# 555_led_blink.net
KiCad netlist of a schematic drawn in EAGLE
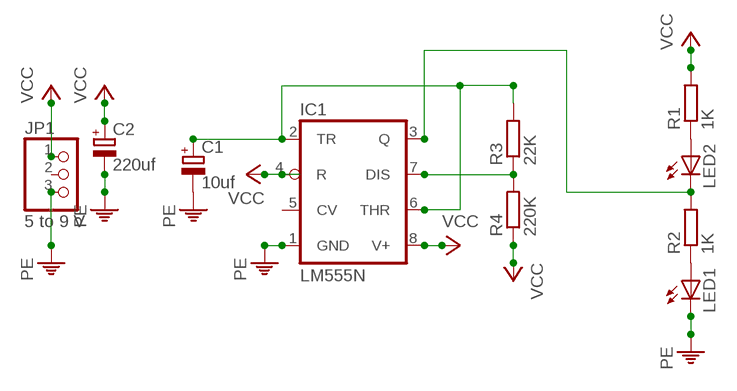
[diagram p0: schematic, sheet 1]

(export (version "E")
  (design (tool "Eeschema 10.0.6"))
  (components
    (comp (ref "C1")
      (value "10uf")
      (footprint "eagle-import:B45181B")
      (libsource (lib "eagle-import") (part "CPOL-EUB45181B"))
    )
    (comp (ref "C2")
      (value "220uf")
      (footprint "eagle-import:B45181B")
      (libsource (lib "eagle-import") (part "CPOL-EUB45181B"))
    )
    (comp (ref "IC1")
      (value "LM555N")
      (footprint "eagle-import:DIL08")
      (libsource (lib "eagle-import") (part "555NLM"))
    )
    (comp (ref "JP1")
      (value "5 to 9 V")
      (footprint "eagle-import:1X03")
      (libsource (lib "eagle-import") (part "PINHD-1X3"))
    )
    (comp (ref "LED1")
      (value "LED5MM")
      (footprint "eagle-import:LED5MM")
      (libsource (lib "eagle-import") (part "LED5MM"))
    )
    (comp (ref "LED2")
      (value "LED5MM")
      (footprint "eagle-import:LED5MM")
      (libsource (lib "eagle-import") (part "LED5MM"))
    )
    (comp (ref "R1")
      (value "1K")
      (footprint "eagle-import:0207_10")
      (libsource (lib "eagle-import") (part "R-EU_0207/10"))
    )
    (comp (ref "R2")
      (value "1K")
      (footprint "eagle-import:0207_10")
      (libsource (lib "eagle-import") (part "R-EU_0207/10"))
    )
    (comp (ref "R3")
      (value "22K")
      (footprint "eagle-import:0207_10")
      (libsource (lib "eagle-import") (part "R-EU_0207/10"))
    )
    (comp (ref "R4")
      (value "220K")
      (footprint "eagle-import:0207_10")
      (libsource (lib "eagle-import") (part "R-EU_0207/10"))
    )
  )
  (nets
    (net (code "1") (name "Net-(IC1-DIS)") (class "Default")
      (node (ref "IC1") (pin "7") (pinfunction "DIS_7") (pintype "input"))
      (node (ref "R3") (pin "1") (pinfunction "1_1") (pintype "passive"))
      (node (ref "R4") (pin "2") (pinfunction "2_2") (pintype "passive"))
    )
    (net (code "2") (name "Net-(IC1-Q)") (class "Default")
      (node (ref "IC1") (pin "3") (pinfunction "Q_3") (pintype "output"))
      (node (ref "LED2") (pin "K") (pinfunction "C_K") (pintype "passive"))
      (node (ref "R2") (pin "2") (pinfunction "2_2") (pintype "passive"))
    )
    (net (code "3") (name "Net-(IC1-THR)") (class "Default")
      (node (ref "C1") (pin "+") (pinfunction "+_+") (pintype "passive"))
      (node (ref "IC1") (pin "2") (pinfunction "TR_2") (pintype "input"))
      (node (ref "IC1") (pin "6") (pinfunction "THR_6") (pintype "input"))
      (node (ref "R3") (pin "2") (pinfunction "2_2") (pintype "passive"))
    )
    (net (code "4") (name "Net-(LED1-PadA)") (class "Default")
      (node (ref "LED1") (pin "A") (pinfunction "A_A") (pintype "passive"))
      (node (ref "R2") (pin "1") (pinfunction "1_1") (pintype "passive"))
    )
    (net (code "5") (name "Net-(LED2-PadA)") (class "Default")
      (node (ref "LED2") (pin "A") (pinfunction "A_A") (pintype "passive"))
      (node (ref "R1") (pin "1") (pinfunction "1_1") (pintype "passive"))
    )
    (net (code "6") (name "PE") (class "Default")
      (node (ref "C1") (pin "-") (pinfunction "-_-") (pintype "passive"))
      (node (ref "C2") (pin "-") (pinfunction "-_-") (pintype "passive"))
      (node (ref "IC1") (pin "1") (pinfunction "GND_1") (pintype "power_in"))
      (node (ref "JP1") (pin "3") (pinfunction "3_3") (pintype "passive"))
      (node (ref "LED1") (pin "K") (pinfunction "C_K") (pintype "passive"))
    )
    (net (code "7") (name "VCC") (class "Default")
      (node (ref "C2") (pin "+") (pinfunction "+_+") (pintype "passive"))
      (node (ref "IC1") (pin "4") (pinfunction "R_4") (pintype "input"))
      (node (ref "IC1") (pin "8") (pinfunction "V+_8") (pintype "power_in"))
      (node (ref "JP1") (pin "1") (pinfunction "1_1") (pintype "passive"))
      (node (ref "R1") (pin "2") (pinfunction "2_2") (pintype "passive"))
      (node (ref "R4") (pin "1") (pinfunction "1_1") (pintype "passive"))
    )
    (net (code "8") (name "unconnected-(IC1-CV-Pad5)") (class "Default")
      (node (ref "IC1") (pin "5") (pinfunction "CV_5") (pintype "input"))
    )
    (net (code "9") (name "unconnected-(JP1-Pad2)") (class "Default")
      (node (ref "JP1") (pin "2") (pinfunction "2_2") (pintype "passive"))
    )
  )
)
